# sche.net
KiCad netlist of a schematic drawn in Altium Designer
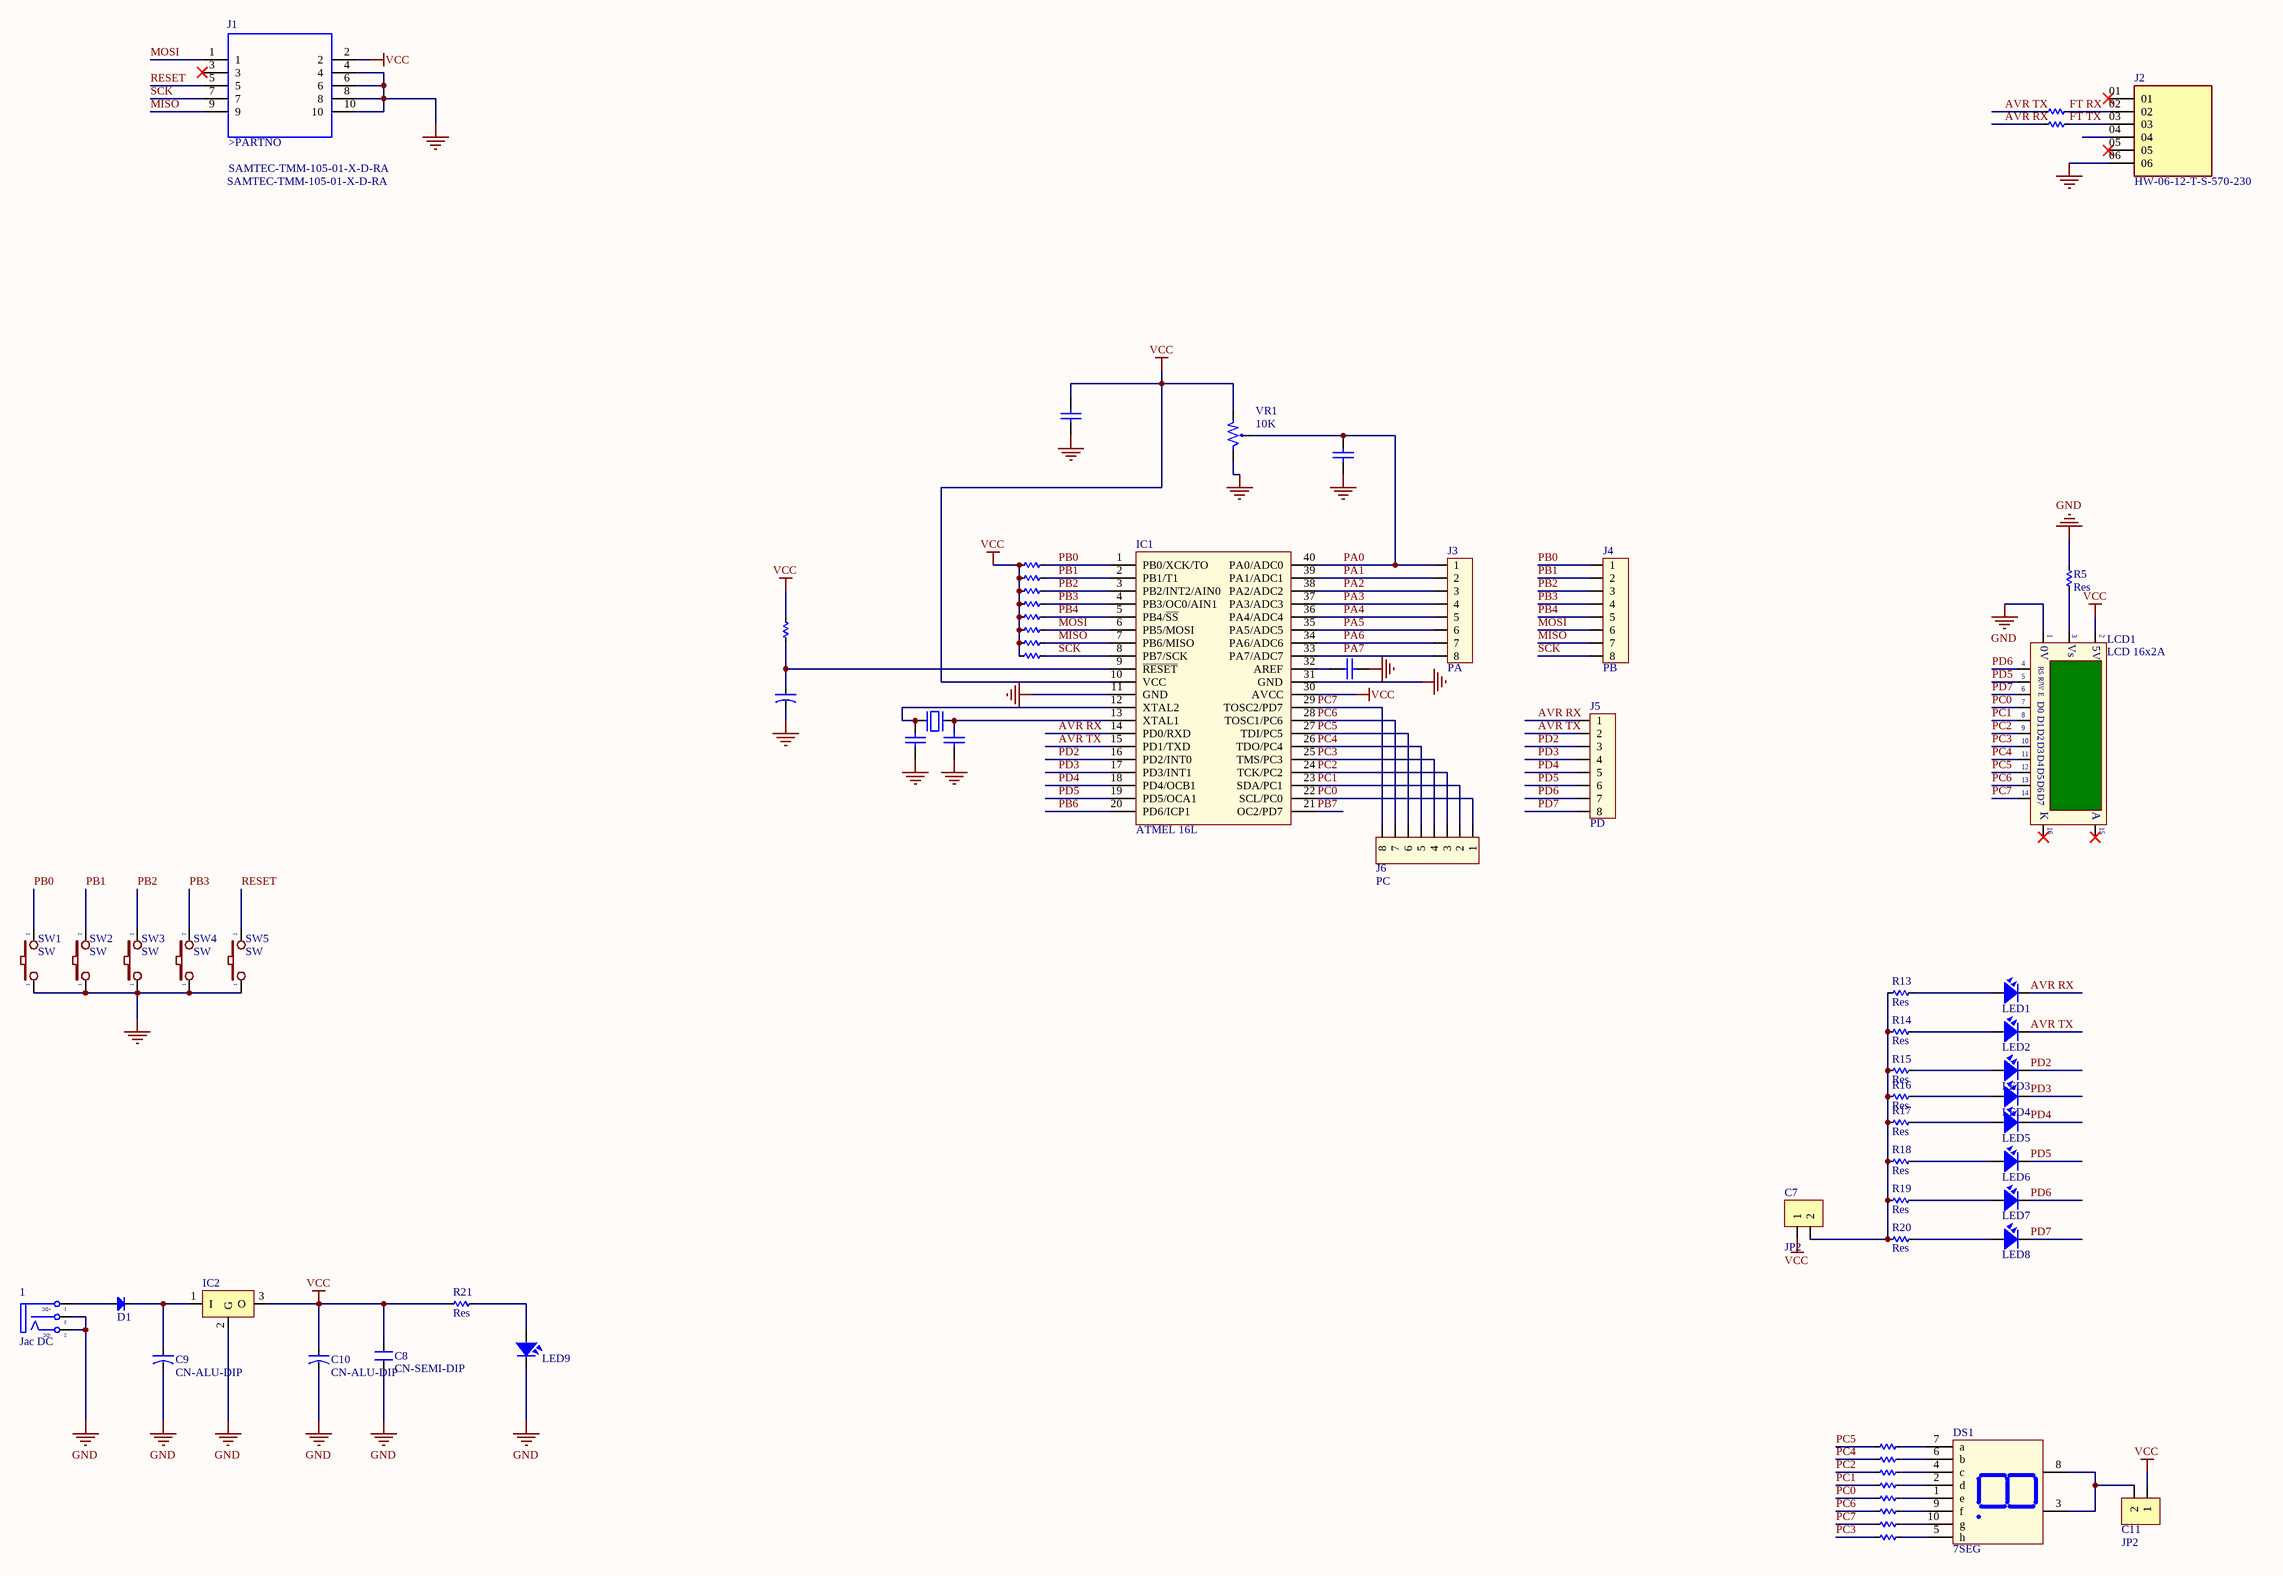
[diagram p0: sche.SchDoc]

(export (version "E")
  (design (tool "Eeschema 10.0.6"))
  (components
    (comp (ref "1")
      (value "Jac DC")
      (footprint "DC0")
      (description "Jac DC input")
      (libsource (lib "Altium Library") (part "DCIN"))
    )
    (comp (ref "C1")
      (value "104")
      (footprint "CNP")
      (description "Capacitor (Semiconductor SIM Model)")
      (fields (field (name "PUBLISHER") "Altium Limited"))
      (libsource (lib "syhaunguyen") (part "Cap Semi"))
    )
    (comp (ref "C2")
      (value "104")
      (footprint "CNP")
      (description "Capacitor (Semiconductor SIM Model)")
      (fields (field (name "PUBLISHER") "Altium Limited"))
      (libsource (lib "syhaunguyen") (part "Cap Semi"))
    )
    (comp (ref "C3")
      (value "104")
      (footprint "CNP")
      (description "Capacitor (Semiconductor SIM Model)")
      (fields (field (name "PUBLISHER") "Altium Limited"))
      (libsource (lib "syhaunguyen") (part "Cap Semi"))
    )
    (comp (ref "C4")
      (value "CN-ALU-DIP")
      (footprint "CA-ALU-2.54")
      (description "Capacitor (Semiconductor SIM Model)")
      (fields (field (name "PUBLISHER") "Altium Limited"))
      (libsource (lib "Altium Library") (part "CN-ALU-DIP"))
    )
    (comp (ref "C5")
      (value "104")
      (footprint "CNP")
      (description "Capacitor (Semiconductor SIM Model)")
      (fields (field (name "PUBLISHER") "Altium Limited"))
      (libsource (lib "syhaunguyen") (part "Cap Semi"))
    )
    (comp (ref "C6")
      (value "104")
      (footprint "CNP")
      (description "Capacitor (Semiconductor SIM Model)")
      (fields (field (name "PUBLISHER") "Altium Limited"))
      (libsource (lib "syhaunguyen") (part "Cap Semi"))
    )
    (comp (ref "C7")
      (value "JP2")
      (footprint "JP2-C1T")
      (description "WR-PHD 2.54 mm Angled Socket Header")
      (fields
        (field (name "MANUFACTURER") "Würth Elektronik eiSos GmbH")
        (field (name "PARTNO") "613002143121")
        (field (name "CREATED BY") "Karrer Zheng")
      )
      (libsource (lib "") (part "JP2_1"))
    )
    (comp (ref "C8")
      (value "CN-SEMI-DIP")
      (footprint "C-SE-7,5x10x9x5x4")
      (description "Capacitor (Semiconductor SIM Model)")
      (fields (field (name "PUBLISHER") "Altium Limited"))
      (libsource (lib "Altium Library") (part "CN-SEMI-DIP"))
    )
    (comp (ref "C9")
      (value "CN-ALU-DIP")
      (footprint "CA-ALU-2.54")
      (description "Capacitor (Semiconductor SIM Model)")
      (fields (field (name "PUBLISHER") "Altium Limited"))
      (libsource (lib "Altium Library") (part "CN-ALU-DIP"))
    )
    (comp (ref "C10")
      (value "CN-ALU-DIP")
      (footprint "CA-ALU-2.54")
      (description "Capacitor (Semiconductor SIM Model)")
      (fields (field (name "PUBLISHER") "Altium Limited"))
      (libsource (lib "Altium Library") (part "CN-ALU-DIP"))
    )
    (comp (ref "C11")
      (value "JP2")
      (footprint "JP2-C1T")
      (description "WR-PHD 2.54 mm Angled Socket Header")
      (fields
        (field (name "MANUFACTURER") "Würth Elektronik eiSos GmbH")
        (field (name "PARTNO") "613002143121")
        (field (name "CREATED BY") "Karrer Zheng")
      )
      (libsource (lib "Altium Library") (part "JP2"))
    )
    (comp (ref "D1")
      (value "Diode")
      (footprint "DIO-1A")
      (description "Default Diode")
      (fields (field (name "PUBLISHER") "Altium Limited"))
      (libsource (lib "Altium Library") (part "Diode"))
    )
    (comp (ref "DS1")
      (value "7SEG")
      (footprint "LED7SEG-1-0.56")
      (description "14.2 mm General Purpose Blue 7-Segment Display: CC, RH DP, Gray Surface")
      (fields (field (name "PUBLISHER") "Altium Limited"))
      (libsource (lib "Altium Library") (part "LED7SEG-1"))
    )
    (comp (ref "IC1")
      (value "ATMEL 16L")
      (footprint "DIP40/W0.6")
      (description "8-Bit AVR Microcontroller with 16K Bytes of In-System Programmable Flash Memory")
      (libsource (lib "My Library") (part "Atmega16L"))
    )
    (comp (ref "IC2")
      (value "LM78xx")
      (footprint "TO220-123")
      (description "Positive Voltage Regulator")
      (fields (field (name "PUBLISHER") "Altium Limited"))
      (libsource (lib "Altium Library") (part "LM78xx"))
    )
    (comp (ref "J1")
      (value "SAMTEC-TMM-105-01-X-D-RA")
      (footprint "SAMTEC-TMM-105-01-X-D-RA")
      (fields (field (name "MF") "Samtec"))
      (libsource (lib "SAMTEC-TMM-105-01-X-D-RA") (part "SAMTEC-TMM-105-01-X-D-RA"))
    )
    (comp (ref "J2")
      (value "HW-06-12-T-S-570-230")
      (footprint "SAMTEC_HW-06-12-T-S-570-230")
      (libsource (lib "HW-06-12-T-S-570-230") (part "HW-06-12-T-S-570-230"))
    )
    (comp (ref "J3")
      (value "PA")
      (footprint "Header8")
      (description "Connector 8")
      (libsource (lib "My Library") (part "Header8"))
    )
    (comp (ref "J4")
      (value "PB")
      (footprint "Header8")
      (description "Connector 8")
      (libsource (lib "My Library") (part "Header8"))
    )
    (comp (ref "J5")
      (value "PD")
      (footprint "Header8")
      (description "Connector 8")
      (libsource (lib "My Library") (part "Header8"))
    )
    (comp (ref "J6")
      (value "PC")
      (footprint "Header8")
      (description "Connector 8")
      (libsource (lib "") (part "Header8_1"))
    )
    (comp (ref "LCD1")
      (value "LCD 16x2A")
      (footprint "JP16-C1T")
      (description "LCD dipslay 16 char, 2 line")
      (libsource (lib "Altium Library") (part "LCD16x2A"))
    )
    (comp (ref "LED1")
      (value "LED")
      (footprint "LED-3MM-YELLOW")
      (description "LED Single colour Green and Red")
      (libsource (lib "Altium Library") (part "LED"))
    )
    (comp (ref "LED2")
      (value "LED")
      (footprint "LED-3MM-YELLOW")
      (description "LED Single colour Green and Red")
      (libsource (lib "Altium Library") (part "LED"))
    )
    (comp (ref "LED3")
      (value "LED")
      (footprint "LED-3MM-YELLOW")
      (description "LED Single colour Green and Red")
      (libsource (lib "Altium Library") (part "LED"))
    )
    (comp (ref "LED4")
      (value "LED")
      (footprint "LED-3MM-YELLOW")
      (description "LED Single colour Green and Red")
      (libsource (lib "Altium Library") (part "LED"))
    )
    (comp (ref "LED5")
      (value "LED")
      (footprint "LED-3MM-YELLOW")
      (description "LED Single colour Green and Red")
      (libsource (lib "Altium Library") (part "LED"))
    )
    (comp (ref "LED6")
      (value "LED")
      (footprint "LED-3MM-YELLOW")
      (description "LED Single colour Green and Red")
      (libsource (lib "Altium Library") (part "LED"))
    )
    (comp (ref "LED7")
      (value "LED")
      (footprint "LED-3MM-YELLOW")
      (description "LED Single colour Green and Red")
      (libsource (lib "Altium Library") (part "LED"))
    )
    (comp (ref "LED8")
      (value "LED")
      (footprint "LED-3MM-YELLOW")
      (description "LED Single colour Green and Red")
      (libsource (lib "Altium Library") (part "LED"))
    )
    (comp (ref "LED9")
      (value "LED")
      (footprint "LED-3MM-YELLOW")
      (description "LED Single colour Green and Red")
      (libsource (lib "Altium Library") (part "LED"))
    )
    (comp (ref "R1")
      (value "10K")
      (footprint "RES-SMD-0805")
      (description "R3")
      (fields
        (field (name "MANUFACTURER") "Generic Components")
        (field (name "PUBLISHER") "Altium Hobart Technology Centre")
      )
      (libsource (lib "Altium Library") (part "Res-SMD"))
    )
    (comp (ref "R2")
      (value "10K")
      (footprint "RES-SMD-0805")
      (description "R3")
      (fields
        (field (name "MANUFACTURER") "Generic Components")
        (field (name "PUBLISHER") "Altium Hobart Technology Centre")
      )
      (libsource (lib "Altium Library") (part "Res-SMD"))
    )
    (comp (ref "R3")
      (value "10K")
      (footprint "RES-SMD-0805")
      (description "R3")
      (fields
        (field (name "MANUFACTURER") "Generic Components")
        (field (name "PUBLISHER") "Altium Hobart Technology Centre")
      )
      (libsource (lib "Altium Library") (part "Res-SMD"))
    )
    (comp (ref "R4")
      (value "Res")
      (footprint "RES-SMD-0805")
      (description "Resistor")
      (fields
        (field (name "MANUFACTURER") "Generic Components")
        (field (name "PUBLISHER") "Altium Hobart Technology Centre")
      )
      (libsource (lib "Altium Library") (part "Res-SMD"))
    )
    (comp (ref "R5")
      (value "Res")
      (footprint "RES-SMD-0805")
      (description "Resistor")
      (fields
        (field (name "MANUFACTURER") "Generic Components")
        (field (name "PUBLISHER") "Altium Hobart Technology Centre")
      )
      (libsource (lib "Altium Library") (part "Res-SMD"))
    )
    (comp (ref "R6")
      (value "Res")
      (footprint "RES-SMD-0805")
      (description "Resistor")
      (fields
        (field (name "MANUFACTURER") "Generic Components")
        (field (name "PUBLISHER") "Altium Hobart Technology Centre")
      )
      (libsource (lib "Altium Library") (part "Res-SMD"))
    )
    (comp (ref "R7")
      (value "Res")
      (footprint "RES-SMD-0805")
      (description "Resistor")
      (fields
        (field (name "MANUFACTURER") "Generic Components")
        (field (name "PUBLISHER") "Altium Hobart Technology Centre")
      )
      (libsource (lib "Altium Library") (part "Res-SMD"))
    )
    (comp (ref "R8")
      (value "Res")
      (footprint "RES-SMD-0805")
      (description "Resistor")
      (fields
        (field (name "MANUFACTURER") "Generic Components")
        (field (name "PUBLISHER") "Altium Hobart Technology Centre")
      )
      (libsource (lib "Altium Library") (part "Res-SMD"))
    )
    (comp (ref "R9")
      (value "Res")
      (footprint "RES-SMD-0805")
      (description "Resistor")
      (fields
        (field (name "MANUFACTURER") "Generic Components")
        (field (name "PUBLISHER") "Altium Hobart Technology Centre")
      )
      (libsource (lib "Altium Library") (part "Res-SMD"))
    )
    (comp (ref "R10")
      (value "Res")
      (footprint "RES-SMD-0805")
      (description "Resistor")
      (fields
        (field (name "MANUFACTURER") "Generic Components")
        (field (name "PUBLISHER") "Altium Hobart Technology Centre")
      )
      (libsource (lib "Altium Library") (part "Res-SMD"))
    )
    (comp (ref "R11")
      (value "Res")
      (footprint "RES-SMD-0805")
      (description "Resistor")
      (fields
        (field (name "MANUFACTURER") "Generic Components")
        (field (name "PUBLISHER") "Altium Hobart Technology Centre")
      )
      (libsource (lib "Altium Library") (part "Res-SMD"))
    )
    (comp (ref "R12")
      (value "Res")
      (footprint "RES-SMD-0805")
      (description "Resistor")
      (fields
        (field (name "MANUFACTURER") "Generic Components")
        (field (name "PUBLISHER") "Altium Hobart Technology Centre")
      )
      (libsource (lib "Altium Library") (part "Res-SMD"))
    )
    (comp (ref "R13")
      (value "Res")
      (footprint "RES-SMD-0805")
      (description "Resistor")
      (fields
        (field (name "MANUFACTURER") "Generic Components")
        (field (name "PUBLISHER") "Altium Hobart Technology Centre")
      )
      (libsource (lib "Altium Library") (part "Res-SMD"))
    )
    (comp (ref "R14")
      (value "Res")
      (footprint "RES-SMD-0805")
      (description "Resistor")
      (fields
        (field (name "MANUFACTURER") "Generic Components")
        (field (name "PUBLISHER") "Altium Hobart Technology Centre")
      )
      (libsource (lib "Altium Library") (part "Res-SMD"))
    )
    (comp (ref "R15")
      (value "Res")
      (footprint "RES-SMD-0805")
      (description "Resistor")
      (fields
        (field (name "MANUFACTURER") "Generic Components")
        (field (name "PUBLISHER") "Altium Hobart Technology Centre")
      )
      (libsource (lib "Altium Library") (part "Res-SMD"))
    )
    (comp (ref "R16")
      (value "Res")
      (footprint "RES-SMD-0805")
      (description "Resistor")
      (fields
        (field (name "MANUFACTURER") "Generic Components")
        (field (name "PUBLISHER") "Altium Hobart Technology Centre")
      )
      (libsource (lib "Altium Library") (part "Res-SMD"))
    )
    (comp (ref "R17")
      (value "Res")
      (footprint "RES-SMD-0805")
      (description "Resistor")
      (fields
        (field (name "MANUFACTURER") "Generic Components")
        (field (name "PUBLISHER") "Altium Hobart Technology Centre")
      )
      (libsource (lib "Altium Library") (part "Res-SMD"))
    )
    (comp (ref "R18")
      (value "Res")
      (footprint "RES-SMD-0805")
      (description "Resistor")
      (fields
        (field (name "MANUFACTURER") "Generic Components")
        (field (name "PUBLISHER") "Altium Hobart Technology Centre")
      )
      (libsource (lib "Altium Library") (part "Res-SMD"))
    )
    (comp (ref "R19")
      (value "Res")
      (footprint "RES-SMD-0805")
      (description "Resistor")
      (fields
        (field (name "MANUFACTURER") "Generic Components")
        (field (name "PUBLISHER") "Altium Hobart Technology Centre")
      )
      (libsource (lib "Altium Library") (part "Res-SMD"))
    )
    (comp (ref "R20")
      (value "Res")
      (footprint "RES-SMD-0805")
      (description "Resistor")
      (fields
        (field (name "MANUFACTURER") "Generic Components")
        (field (name "PUBLISHER") "Altium Hobart Technology Centre")
      )
      (libsource (lib "Altium Library") (part "Res-SMD"))
    )
    (comp (ref "R21")
      (value "Res")
      (footprint "RES-SMD-0805")
      (description "Resistor")
      (fields
        (field (name "MANUFACTURER") "Generic Components")
        (field (name "PUBLISHER") "Altium Hobart Technology Centre")
      )
      (libsource (lib "Altium Library") (part "Res-SMD"))
    )
    (comp (ref "R22")
      (value "Res")
      (footprint "RES-SMD-0805")
      (description "Resistor")
      (fields
        (field (name "MANUFACTURER") "Generic Components")
        (field (name "PUBLISHER") "Altium Hobart Technology Centre")
      )
      (libsource (lib "Altium Library") (part "Res-SMD"))
    )
    (comp (ref "R23")
      (value "Res")
      (footprint "RES-SMD-0805")
      (description "Resistor")
      (fields
        (field (name "MANUFACTURER") "Generic Components")
        (field (name "PUBLISHER") "Altium Hobart Technology Centre")
      )
      (libsource (lib "Altium Library") (part "Res-SMD"))
    )
    (comp (ref "R24")
      (value "Res")
      (footprint "RES-SMD-0805")
      (description "Resistor")
      (fields
        (field (name "MANUFACTURER") "Generic Components")
        (field (name "PUBLISHER") "Altium Hobart Technology Centre")
      )
      (libsource (lib "Altium Library") (part "Res-SMD"))
    )
    (comp (ref "R25")
      (value "Res")
      (footprint "RES-SMD-0805")
      (description "Resistor")
      (fields
        (field (name "MANUFACTURER") "Generic Components")
        (field (name "PUBLISHER") "Altium Hobart Technology Centre")
      )
      (libsource (lib "Altium Library") (part "Res-SMD"))
    )
    (comp (ref "R26")
      (value "Res")
      (footprint "RES-SMD-0805")
      (description "Resistor")
      (fields
        (field (name "MANUFACTURER") "Generic Components")
        (field (name "PUBLISHER") "Altium Hobart Technology Centre")
      )
      (libsource (lib "Altium Library") (part "Res-SMD"))
    )
    (comp (ref "R27")
      (value "Res")
      (footprint "RES-SMD-0805")
      (description "Resistor")
      (fields
        (field (name "MANUFACTURER") "Generic Components")
        (field (name "PUBLISHER") "Altium Hobart Technology Centre")
      )
      (libsource (lib "Altium Library") (part "Res-SMD"))
    )
    (comp (ref "R28")
      (value "Res")
      (footprint "RES-SMD-0805")
      (description "Resistor")
      (fields
        (field (name "MANUFACTURER") "Generic Components")
        (field (name "PUBLISHER") "Altium Hobart Technology Centre")
      )
      (libsource (lib "Altium Library") (part "Res-SMD"))
    )
    (comp (ref "R29")
      (value "Res")
      (footprint "RES-SMD-0805")
      (description "Resistor")
      (fields
        (field (name "MANUFACTURER") "Generic Components")
        (field (name "PUBLISHER") "Altium Hobart Technology Centre")
      )
      (libsource (lib "Altium Library") (part "Res-SMD"))
    )
    (comp (ref "SW1")
      (value "SW")
      (footprint "SW2")
      (description "Switch button 2 pin")
      (libsource (lib "My Library") (part "SW2"))
    )
    (comp (ref "SW2")
      (value "SW")
      (footprint "SW2")
      (description "Switch button 2 pin")
      (libsource (lib "My Library") (part "SW2"))
    )
    (comp (ref "SW3")
      (value "SW")
      (footprint "SW2")
      (description "Switch button 2 pin")
      (libsource (lib "My Library") (part "SW2"))
    )
    (comp (ref "SW4")
      (value "SW")
      (footprint "SW2")
      (description "Switch button 2 pin")
      (libsource (lib "My Library") (part "SW2"))
    )
    (comp (ref "SW5")
      (value "SW")
      (footprint "SW2")
      (description "Switch button 2 pin")
      (libsource (lib "My Library") (part "SW2"))
    )
    (comp (ref "VR1")
      (value "10K")
      (footprint "VR")
      (description "Var Resistor")
      (libsource (lib "My Library") (part "VR1"))
    )
    (comp (ref "X1")
      (value "12Mhz")
      (footprint "XT2")
      (description "Crystal, 32.768 KHz, -40 to 85 degC, 3.2 x 1.5 x 0.9 mm SMD")
      (libsource (lib "Altium Library") (part "XT2"))
    )
  )
  (nets
    (net (code "1") (name "/AVR RX") (class "Default")
      (node (ref "IC1") (pin "14") (pinfunction "PD0/RXD_14") (pintype "passive"))
      (node (ref "J5") (pin "1") (pinfunction "1_1") (pintype "passive"))
      (node (ref "LED1") (pin "2") (pinfunction "2_2") (pintype "passive"))
      (node (ref "R2") (pin "2") (pinfunction "2_2") (pintype "passive"))
    )
    (net (code "2") (name "/AVR TX") (class "Default")
      (node (ref "IC1") (pin "15") (pinfunction "PD1/TXD_15") (pintype "passive"))
      (node (ref "J5") (pin "2") (pinfunction "2_2") (pintype "passive"))
      (node (ref "LED2") (pin "2") (pinfunction "2_2") (pintype "passive"))
      (node (ref "R1") (pin "2") (pinfunction "2_2") (pintype "passive"))
    )
    (net (code "3") (name "/FT RX") (class "Default")
      (node (ref "J2") (pin "02") (pinfunction "02_02") (pintype "passive"))
      (node (ref "R1") (pin "1") (pinfunction "1_1") (pintype "passive"))
    )
    (net (code "4") (name "/FT TX") (class "Default")
      (node (ref "J2") (pin "03") (pinfunction "03_03") (pintype "passive"))
      (node (ref "R2") (pin "1") (pinfunction "1_1") (pintype "passive"))
    )
    (net (code "5") (name "/MISO") (class "Default")
      (node (ref "IC1") (pin "7") (pinfunction "PB6/MISO_7") (pintype "passive"))
      (node (ref "J1") (pin "9") (pinfunction "9_9") (pintype "passive"))
      (node (ref "J4") (pin "7") (pinfunction "7_7") (pintype "passive"))
      (node (ref "R11") (pin "1") (pinfunction "1_1") (pintype "passive"))
    )
    (net (code "6") (name "/MOSI") (class "Default")
      (node (ref "IC1") (pin "6") (pinfunction "PB5/MOSI_6") (pintype "passive"))
      (node (ref "J1") (pin "1") (pinfunction "1_1") (pintype "passive"))
      (node (ref "J4") (pin "6") (pinfunction "6_6") (pintype "passive"))
      (node (ref "R9") (pin "1") (pinfunction "1_1") (pintype "passive"))
    )
    (net (code "7") (name "/PA0") (class "Default")
      (node (ref "C2") (pin "1") (pinfunction "1_1") (pintype "passive"))
      (node (ref "IC1") (pin "40") (pinfunction "PA0/ADC0_40") (pintype "passive"))
      (node (ref "J3") (pin "1") (pinfunction "1_1") (pintype "passive"))
      (node (ref "VR1") (pin "2") (pinfunction "2_2") (pintype "passive"))
    )
    (net (code "8") (name "/PA1") (class "Default")
      (node (ref "IC1") (pin "39") (pinfunction "PA1/ADC1_39") (pintype "passive"))
      (node (ref "J3") (pin "2") (pinfunction "2_2") (pintype "passive"))
    )
    (net (code "9") (name "/PA2") (class "Default")
      (node (ref "IC1") (pin "38") (pinfunction "PA2/ADC2_38") (pintype "passive"))
      (node (ref "J3") (pin "3") (pinfunction "3_3") (pintype "passive"))
    )
    (net (code "10") (name "/PA3") (class "Default")
      (node (ref "IC1") (pin "37") (pinfunction "PA3/ADC3_37") (pintype "passive"))
      (node (ref "J3") (pin "4") (pinfunction "4_4") (pintype "passive"))
    )
    (net (code "11") (name "/PA4") (class "Default")
      (node (ref "IC1") (pin "36") (pinfunction "PA4/ADC4_36") (pintype "passive"))
      (node (ref "J3") (pin "5") (pinfunction "5_5") (pintype "passive"))
    )
    (net (code "12") (name "/PA5") (class "Default")
      (node (ref "IC1") (pin "35") (pinfunction "PA5/ADC5_35") (pintype "passive"))
      (node (ref "J3") (pin "6") (pinfunction "6_6") (pintype "passive"))
    )
    (net (code "13") (name "/PA6") (class "Default")
      (node (ref "IC1") (pin "34") (pinfunction "PA6/ADC6_34") (pintype "passive"))
      (node (ref "J3") (pin "7") (pinfunction "7_7") (pintype "passive"))
    )
    (net (code "14") (name "/PA7") (class "Default")
      (node (ref "IC1") (pin "33") (pinfunction "PA7/ADC7_33") (pintype "passive"))
      (node (ref "J3") (pin "8") (pinfunction "8_8") (pintype "passive"))
    )
    (net (code "15") (name "/PB0") (class "Default")
      (node (ref "IC1") (pin "1") (pinfunction "PB0/XCK/TO_1") (pintype "passive"))
      (node (ref "J4") (pin "1") (pinfunction "1_1") (pintype "passive"))
      (node (ref "R3") (pin "1") (pinfunction "1_1") (pintype "passive"))
      (node (ref "SW1") (pin "2") (pinfunction "2_2") (pintype "passive"))
    )
    (net (code "16") (name "/PB1") (class "Default")
      (node (ref "IC1") (pin "2") (pinfunction "PB1/T1_2") (pintype "passive"))
      (node (ref "J4") (pin "2") (pinfunction "2_2") (pintype "passive"))
      (node (ref "R4") (pin "1") (pinfunction "1_1") (pintype "passive"))
      (node (ref "SW2") (pin "2") (pinfunction "2_2") (pintype "passive"))
    )
    (net (code "17") (name "/PB2") (class "Default")
      (node (ref "IC1") (pin "3") (pinfunction "PB2/INT2/AIN0_3") (pintype "passive"))
      (node (ref "J4") (pin "3") (pinfunction "3_3") (pintype "passive"))
      (node (ref "R6") (pin "1") (pinfunction "1_1") (pintype "passive"))
      (node (ref "SW3") (pin "2") (pinfunction "2_2") (pintype "passive"))
    )
    (net (code "18") (name "/PB3") (class "Default")
      (node (ref "IC1") (pin "4") (pinfunction "PB3/OC0/AIN1_4") (pintype "passive"))
      (node (ref "J4") (pin "4") (pinfunction "4_4") (pintype "passive"))
      (node (ref "R7") (pin "1") (pinfunction "1_1") (pintype "passive"))
      (node (ref "SW4") (pin "2") (pinfunction "2_2") (pintype "passive"))
    )
    (net (code "19") (name "/PB4") (class "Default")
      (node (ref "IC1") (pin "5") (pinfunction "PB4/~{SS}_5") (pintype "passive"))
      (node (ref "J4") (pin "5") (pinfunction "5_5") (pintype "passive"))
      (node (ref "R8") (pin "1") (pinfunction "1_1") (pintype "passive"))
    )
    (net (code "20") (name "/PB6") (class "Default")
      (node (ref "IC1") (pin "20") (pinfunction "PD6/ICP1_20") (pintype "passive"))
    )
    (net (code "21") (name "/PB7") (class "Default")
      (node (ref "IC1") (pin "21") (pinfunction "OC2/PD7_21") (pintype "passive"))
    )
    (net (code "22") (name "/PC0") (class "Default")
      (node (ref "IC1") (pin "22") (pinfunction "SCL/PC0_22") (pintype "passive"))
      (node (ref "J6") (pin "1") (pinfunction "1_1") (pintype "passive"))
      (node (ref "LCD1") (pin "7") (pinfunction "D0_7") (pintype "passive"))
      (node (ref "R26") (pin "2") (pinfunction "2_2") (pintype "passive"))
    )
    (net (code "23") (name "/PC1") (class "Default")
      (node (ref "IC1") (pin "23") (pinfunction "SDA/PC1_23") (pintype "passive"))
      (node (ref "J6") (pin "2") (pinfunction "2_2") (pintype "passive"))
      (node (ref "LCD1") (pin "8") (pinfunction "D1_8") (pintype "passive"))
      (node (ref "R25") (pin "2") (pinfunction "2_2") (pintype "passive"))
    )
    (net (code "24") (name "/PC2") (class "Default")
      (node (ref "IC1") (pin "24") (pinfunction "TCK/PC2_24") (pintype "passive"))
      (node (ref "J6") (pin "3") (pinfunction "3_3") (pintype "passive"))
      (node (ref "LCD1") (pin "9") (pinfunction "D2_9") (pintype "passive"))
      (node (ref "R24") (pin "2") (pinfunction "2_2") (pintype "passive"))
    )
    (net (code "25") (name "/PC3") (class "Default")
      (node (ref "IC1") (pin "25") (pinfunction "TMS/PC3_25") (pintype "passive"))
      (node (ref "J6") (pin "4") (pinfunction "4_4") (pintype "passive"))
      (node (ref "LCD1") (pin "10") (pinfunction "D3_10") (pintype "passive"))
      (node (ref "R29") (pin "2") (pinfunction "2_2") (pintype "passive"))
    )
    (net (code "26") (name "/PC4") (class "Default")
      (node (ref "IC1") (pin "26") (pinfunction "TDO/PC4_26") (pintype "passive"))
      (node (ref "J6") (pin "5") (pinfunction "5_5") (pintype "passive"))
      (node (ref "LCD1") (pin "11") (pinfunction "D4_11") (pintype "passive"))
      (node (ref "R23") (pin "2") (pinfunction "2_2") (pintype "passive"))
    )
    (net (code "27") (name "/PC5") (class "Default")
      (node (ref "IC1") (pin "27") (pinfunction "TDI/PC5_27") (pintype "passive"))
      (node (ref "J6") (pin "6") (pinfunction "6_6") (pintype "passive"))
      (node (ref "LCD1") (pin "12") (pinfunction "D5_12") (pintype "passive"))
      (node (ref "R22") (pin "2") (pinfunction "2_2") (pintype "passive"))
    )
    (net (code "28") (name "/PC6") (class "Default")
      (node (ref "IC1") (pin "28") (pinfunction "TOSC1/PC6_28") (pintype "passive"))
      (node (ref "J6") (pin "7") (pinfunction "7_7") (pintype "passive"))
      (node (ref "LCD1") (pin "13") (pinfunction "D6_13") (pintype "passive"))
      (node (ref "R27") (pin "2") (pinfunction "2_2") (pintype "passive"))
    )
    (net (code "29") (name "/PC7") (class "Default")
      (node (ref "IC1") (pin "29") (pinfunction "TOSC2/PD7_29") (pintype "passive"))
      (node (ref "J6") (pin "8") (pinfunction "8_8") (pintype "passive"))
      (node (ref "LCD1") (pin "14") (pinfunction "D7_14") (pintype "passive"))
      (node (ref "R28") (pin "2") (pinfunction "2_2") (pintype "passive"))
    )
    (net (code "30") (name "/PD2") (class "Default")
      (node (ref "IC1") (pin "16") (pinfunction "PD2/INT0_16") (pintype "passive"))
      (node (ref "J5") (pin "3") (pinfunction "3_3") (pintype "passive"))
      (node (ref "LED3") (pin "2") (pinfunction "2_2") (pintype "passive"))
    )
    (net (code "31") (name "/PD3") (class "Default")
      (node (ref "IC1") (pin "17") (pinfunction "PD3/INT1_17") (pintype "passive"))
      (node (ref "J5") (pin "4") (pinfunction "4_4") (pintype "passive"))
      (node (ref "LED4") (pin "2") (pinfunction "2_2") (pintype "passive"))
    )
    (net (code "32") (name "/PD4") (class "Default")
      (node (ref "IC1") (pin "18") (pinfunction "PD4/OCB1_18") (pintype "passive"))
      (node (ref "J5") (pin "5") (pinfunction "5_5") (pintype "passive"))
      (node (ref "LED5") (pin "2") (pinfunction "2_2") (pintype "passive"))
    )
    (net (code "33") (name "/PD5") (class "Default")
      (node (ref "IC1") (pin "19") (pinfunction "PD5/OCA1_19") (pintype "passive"))
      (node (ref "J5") (pin "6") (pinfunction "6_6") (pintype "passive"))
      (node (ref "LCD1") (pin "5") (pinfunction "R/~{W}_5") (pintype "passive"))
      (node (ref "LED6") (pin "2") (pinfunction "2_2") (pintype "passive"))
    )
    (net (code "34") (name "/PD6") (class "Default")
      (node (ref "J5") (pin "7") (pinfunction "7_7") (pintype "passive"))
      (node (ref "LCD1") (pin "4") (pinfunction "RS_4") (pintype "passive"))
      (node (ref "LED7") (pin "2") (pinfunction "2_2") (pintype "passive"))
    )
    (net (code "35") (name "/PD7") (class "Default")
      (node (ref "J5") (pin "8") (pinfunction "8_8") (pintype "passive"))
      (node (ref "LCD1") (pin "6") (pinfunction "~{EN}_6") (pintype "passive"))
      (node (ref "LED8") (pin "2") (pinfunction "2_2") (pintype "passive"))
    )
    (net (code "36") (name "/RESET") (class "Default")
      (node (ref "J1") (pin "5") (pinfunction "5_5") (pintype "passive"))
      (node (ref "SW5") (pin "2") (pinfunction "2_2") (pintype "passive"))
    )
    (net (code "37") (name "/SCK") (class "Default")
      (node (ref "IC1") (pin "8") (pinfunction "PB7/SCK_8") (pintype "passive"))
      (node (ref "J1") (pin "7") (pinfunction "7_7") (pintype "passive"))
      (node (ref "J4") (pin "8") (pinfunction "8_8") (pintype "passive"))
      (node (ref "R12") (pin "1") (pinfunction "1_1") (pintype "passive"))
    )
    (net (code "38") (name "GND") (class "Default")
      (node (ref "1") (pin "2") (pinfunction "TN_2") (pintype "passive"))
      (node (ref "1") (pin "3") (pinfunction "S_3") (pintype "power_in"))
      (node (ref "C1") (pin "2") (pinfunction "2_2") (pintype "passive"))
      (node (ref "C10") (pin "2") (pinfunction "2_2") (pintype "passive"))
      (node (ref "C2") (pin "2") (pinfunction "2_2") (pintype "passive"))
      (node (ref "C3") (pin "1") (pinfunction "1_1") (pintype "passive"))
      (node (ref "C4") (pin "2") (pinfunction "2_2") (pintype "passive"))
      (node (ref "C5") (pin "1") (pinfunction "1_1") (pintype "passive"))
      (node (ref "C6") (pin "1") (pinfunction "1_1") (pintype "passive"))
      (node (ref "C8") (pin "1") (pinfunction "1_1") (pintype "passive"))
      (node (ref "C9") (pin "2") (pinfunction "2_2") (pintype "passive"))
      (node (ref "IC1") (pin "11") (pinfunction "GND_11") (pintype "passive"))
      (node (ref "IC1") (pin "31") (pinfunction "GND_31") (pintype "passive"))
      (node (ref "IC2") (pin "2") (pinfunction "G_2") (pintype "power_in"))
      (node (ref "J1") (pin "10") (pinfunction "10_10") (pintype "passive"))
      (node (ref "J1") (pin "4") (pinfunction "4_4") (pintype "passive"))
      (node (ref "J1") (pin "6") (pinfunction "6_6") (pintype "passive"))
      (node (ref "J1") (pin "8") (pinfunction "8_8") (pintype "passive"))
      (node (ref "J2") (pin "06") (pinfunction "06_06") (pintype "passive"))
      (node (ref "LCD1") (pin "1") (pinfunction "GND_1") (pintype "passive"))
      (node (ref "LED9") (pin "2") (pinfunction "2_2") (pintype "passive"))
      (node (ref "R5") (pin "1") (pinfunction "1_1") (pintype "passive"))
      (node (ref "SW1") (pin "1") (pinfunction "1_1") (pintype "passive"))
      (node (ref "SW2") (pin "1") (pinfunction "1_1") (pintype "passive"))
      (node (ref "SW3") (pin "1") (pinfunction "1_1") (pintype "passive"))
      (node (ref "SW4") (pin "1") (pinfunction "1_1") (pintype "passive"))
      (node (ref "SW5") (pin "1") (pinfunction "1_1") (pintype "passive"))
      (node (ref "VR1") (pin "3") (pinfunction "3_3") (pintype "passive"))
    )
    (net (code "39") (name "Net-(1-T)") (class "Default")
      (node (ref "1") (pin "1") (pinfunction "T_1") (pintype "passive"))
      (node (ref "D1") (pin "1") (pinfunction "A_1") (pintype "passive"))
    )
    (net (code "40") (name "Net-(C7-Pad2)") (class "Default")
      (node (ref "C7") (pin "2") (pinfunction "2_2") (pintype "passive"))
      (node (ref "R13") (pin "2") (pinfunction "2_2") (pintype "passive"))
      (node (ref "R14") (pin "2") (pinfunction "2_2") (pintype "passive"))
      (node (ref "R15") (pin "2") (pinfunction "2_2") (pintype "passive"))
      (node (ref "R16") (pin "2") (pinfunction "2_2") (pintype "passive"))
      (node (ref "R17") (pin "2") (pinfunction "2_2") (pintype "passive"))
      (node (ref "R18") (pin "2") (pinfunction "2_2") (pintype "passive"))
      (node (ref "R19") (pin "2") (pinfunction "2_2") (pintype "passive"))
      (node (ref "R20") (pin "2") (pinfunction "2_2") (pintype "passive"))
    )
    (net (code "41") (name "Net-(C11-Pad2)") (class "Default")
      (node (ref "C11") (pin "2") (pinfunction "2_2") (pintype "passive"))
      (node (ref "DS1") (pin "3") (pinfunction "Vcc_3") (pintype "passive"))
      (node (ref "DS1") (pin "8") (pinfunction "Vcc_8") (pintype "passive"))
    )
    (net (code "42") (name "Net-(D1-K)") (class "Default")
      (node (ref "C9") (pin "1") (pinfunction "1_1") (pintype "passive"))
      (node (ref "D1") (pin "2") (pinfunction "K_2") (pintype "passive"))
      (node (ref "IC2") (pin "1") (pinfunction "I_1") (pintype "power_in"))
    )
    (net (code "43") (name "Net-(DS1-a)") (class "Default")
      (node (ref "DS1") (pin "7") (pinfunction "a_7") (pintype "passive"))
      (node (ref "R22") (pin "1") (pinfunction "1_1") (pintype "passive"))
    )
    (net (code "44") (name "Net-(DS1-b)") (class "Default")
      (node (ref "DS1") (pin "6") (pinfunction "b_6") (pintype "passive"))
      (node (ref "R23") (pin "1") (pinfunction "1_1") (pintype "passive"))
    )
    (net (code "45") (name "Net-(DS1-c)") (class "Default")
      (node (ref "DS1") (pin "4") (pinfunction "c_4") (pintype "passive"))
      (node (ref "R24") (pin "1") (pinfunction "1_1") (pintype "passive"))
    )
    (net (code "46") (name "Net-(DS1-d)") (class "Default")
      (node (ref "DS1") (pin "2") (pinfunction "d_2") (pintype "passive"))
      (node (ref "R25") (pin "1") (pinfunction "1_1") (pintype "passive"))
    )
    (net (code "47") (name "Net-(DS1-e)") (class "Default")
      (node (ref "DS1") (pin "1") (pinfunction "e_1") (pintype "passive"))
      (node (ref "R26") (pin "1") (pinfunction "1_1") (pintype "passive"))
    )
    (net (code "48") (name "Net-(DS1-f)") (class "Default")
      (node (ref "DS1") (pin "9") (pinfunction "f_9") (pintype "passive"))
      (node (ref "R27") (pin "1") (pinfunction "1_1") (pintype "passive"))
    )
    (net (code "49") (name "Net-(DS1-g)") (class "Default")
      (node (ref "DS1") (pin "10") (pinfunction "g_10") (pintype "passive"))
      (node (ref "R28") (pin "1") (pinfunction "1_1") (pintype "passive"))
    )
    (net (code "50") (name "Net-(DS1-h)") (class "Default")
      (node (ref "DS1") (pin "5") (pinfunction "h_5") (pintype "passive"))
      (node (ref "R29") (pin "1") (pinfunction "1_1") (pintype "passive"))
    )
    (net (code "51") (name "Net-(IC1-AREF)") (class "Default")
      (node (ref "C3") (pin "2") (pinfunction "2_2") (pintype "passive"))
      (node (ref "IC1") (pin "32") (pinfunction "AREF_32") (pintype "passive"))
    )
    (net (code "52") (name "Net-(IC1-XTAL1)") (class "Default")
      (node (ref "C6") (pin "2") (pinfunction "2_2") (pintype "passive"))
      (node (ref "IC1") (pin "13") (pinfunction "XTAL1_13") (pintype "passive"))
      (node (ref "X1") (pin "2") (pinfunction "2_2") (pintype "passive"))
    )
    (net (code "53") (name "Net-(IC1-XTAL2)") (class "Default")
      (node (ref "C5") (pin "2") (pinfunction "2_2") (pintype "passive"))
      (node (ref "IC1") (pin "12") (pinfunction "XTAL2_12") (pintype "passive"))
      (node (ref "X1") (pin "1") (pinfunction "1_1") (pintype "passive"))
    )
    (net (code "54") (name "Net-(IC1-~{RESET})") (class "Default")
      (node (ref "C4") (pin "1") (pinfunction "1_1") (pintype "passive"))
      (node (ref "IC1") (pin "9") (pinfunction "~{RESET}_9") (pintype "passive"))
      (node (ref "R10") (pin "2") (pinfunction "2_2") (pintype "passive"))
    )
    (net (code "55") (name "Net-(LCD1-VEE)") (class "Default")
      (node (ref "LCD1") (pin "3") (pinfunction "VEE_3") (pintype "passive"))
      (node (ref "R5") (pin "2") (pinfunction "2_2") (pintype "passive"))
    )
    (net (code "56") (name "Net-(LED1-Pad1)") (class "Default")
      (node (ref "LED1") (pin "1") (pinfunction "1_1") (pintype "passive"))
      (node (ref "R13") (pin "1") (pinfunction "1_1") (pintype "passive"))
    )
    (net (code "57") (name "Net-(LED2-Pad1)") (class "Default")
      (node (ref "LED2") (pin "1") (pinfunction "1_1") (pintype "passive"))
      (node (ref "R14") (pin "1") (pinfunction "1_1") (pintype "passive"))
    )
    (net (code "58") (name "Net-(LED3-Pad1)") (class "Default")
      (node (ref "LED3") (pin "1") (pinfunction "1_1") (pintype "passive"))
      (node (ref "R15") (pin "1") (pinfunction "1_1") (pintype "passive"))
    )
    (net (code "59") (name "Net-(LED4-Pad1)") (class "Default")
      (node (ref "LED4") (pin "1") (pinfunction "1_1") (pintype "passive"))
      (node (ref "R16") (pin "1") (pinfunction "1_1") (pintype "passive"))
    )
    (net (code "60") (name "Net-(LED5-Pad1)") (class "Default")
      (node (ref "LED5") (pin "1") (pinfunction "1_1") (pintype "passive"))
      (node (ref "R17") (pin "1") (pinfunction "1_1") (pintype "passive"))
    )
    (net (code "61") (name "Net-(LED6-Pad1)") (class "Default")
      (node (ref "LED6") (pin "1") (pinfunction "1_1") (pintype "passive"))
      (node (ref "R18") (pin "1") (pinfunction "1_1") (pintype "passive"))
    )
    (net (code "62") (name "Net-(LED7-Pad1)") (class "Default")
      (node (ref "LED7") (pin "1") (pinfunction "1_1") (pintype "passive"))
      (node (ref "R19") (pin "1") (pinfunction "1_1") (pintype "passive"))
    )
    (net (code "63") (name "Net-(LED8-Pad1)") (class "Default")
      (node (ref "LED8") (pin "1") (pinfunction "1_1") (pintype "passive"))
      (node (ref "R20") (pin "1") (pinfunction "1_1") (pintype "passive"))
    )
    (net (code "64") (name "Net-(LED9-Pad1)") (class "Default")
      (node (ref "LED9") (pin "1") (pinfunction "1_1") (pintype "passive"))
      (node (ref "R21") (pin "1") (pinfunction "1_1") (pintype "passive"))
    )
    (net (code "65") (name "VCC") (class "Default")
      (node (ref "C1") (pin "1") (pinfunction "1_1") (pintype "passive"))
      (node (ref "C10") (pin "1") (pinfunction "1_1") (pintype "passive"))
      (node (ref "C11") (pin "1") (pinfunction "1_1") (pintype "passive"))
      (node (ref "C7") (pin "1") (pinfunction "1_1") (pintype "passive"))
      (node (ref "C8") (pin "2") (pinfunction "2_2") (pintype "passive"))
      (node (ref "IC1") (pin "10") (pinfunction "VCC_10") (pintype "passive"))
      (node (ref "IC1") (pin "30") (pinfunction "AVCC_30") (pintype "passive"))
      (node (ref "IC2") (pin "3") (pinfunction "O_3") (pintype "power_in"))
      (node (ref "J1") (pin "2") (pinfunction "2_2") (pintype "passive"))
      (node (ref "LCD1") (pin "2") (pinfunction "VDD_2") (pintype "passive"))
      (node (ref "R10") (pin "1") (pinfunction "1_1") (pintype "passive"))
      (node (ref "R11") (pin "2") (pinfunction "2_2") (pintype "passive"))
      (node (ref "R12") (pin "2") (pinfunction "2_2") (pintype "passive"))
      (node (ref "R21") (pin "2") (pinfunction "2_2") (pintype "passive"))
      (node (ref "R3") (pin "2") (pinfunction "2_2") (pintype "passive"))
      (node (ref "R4") (pin "2") (pinfunction "2_2") (pintype "passive"))
      (node (ref "R6") (pin "2") (pinfunction "2_2") (pintype "passive"))
      (node (ref "R7") (pin "2") (pinfunction "2_2") (pintype "passive"))
      (node (ref "R8") (pin "2") (pinfunction "2_2") (pintype "passive"))
      (node (ref "R9") (pin "2") (pinfunction "2_2") (pintype "passive"))
      (node (ref "VR1") (pin "1") (pinfunction "1_1") (pintype "passive"))
    )
    (net (code "66") (name "unconnected-(J1-Pad3)") (class "Default")
      (node (ref "J1") (pin "3") (pinfunction "3_3") (pintype "passive+no_connect"))
    )
    (net (code "67") (name "unconnected-(J2-Pad01)") (class "Default")
      (node (ref "J2") (pin "01") (pinfunction "01_01") (pintype "passive+no_connect"))
    )
    (net (code "68") (name "unconnected-(J2-Pad04)") (class "Default")
      (node (ref "J2") (pin "04") (pinfunction "04_04") (pintype "passive"))
    )
    (net (code "69") (name "unconnected-(J2-Pad05)") (class "Default")
      (node (ref "J2") (pin "05") (pinfunction "05_05") (pintype "passive+no_connect"))
    )
    (net (code "70") (name "unconnected-(LCD1-A-Pad15)") (class "Default")
      (node (ref "LCD1") (pin "15") (pinfunction "A_15") (pintype "passive+no_connect"))
    )
    (net (code "71") (name "unconnected-(LCD1-K-Pad16)") (class "Default")
      (node (ref "LCD1") (pin "16") (pinfunction "K_16") (pintype "passive+no_connect"))
    )
  )
)
